# shield.net
KiCad netlist of a schematic drawn in EAGLE
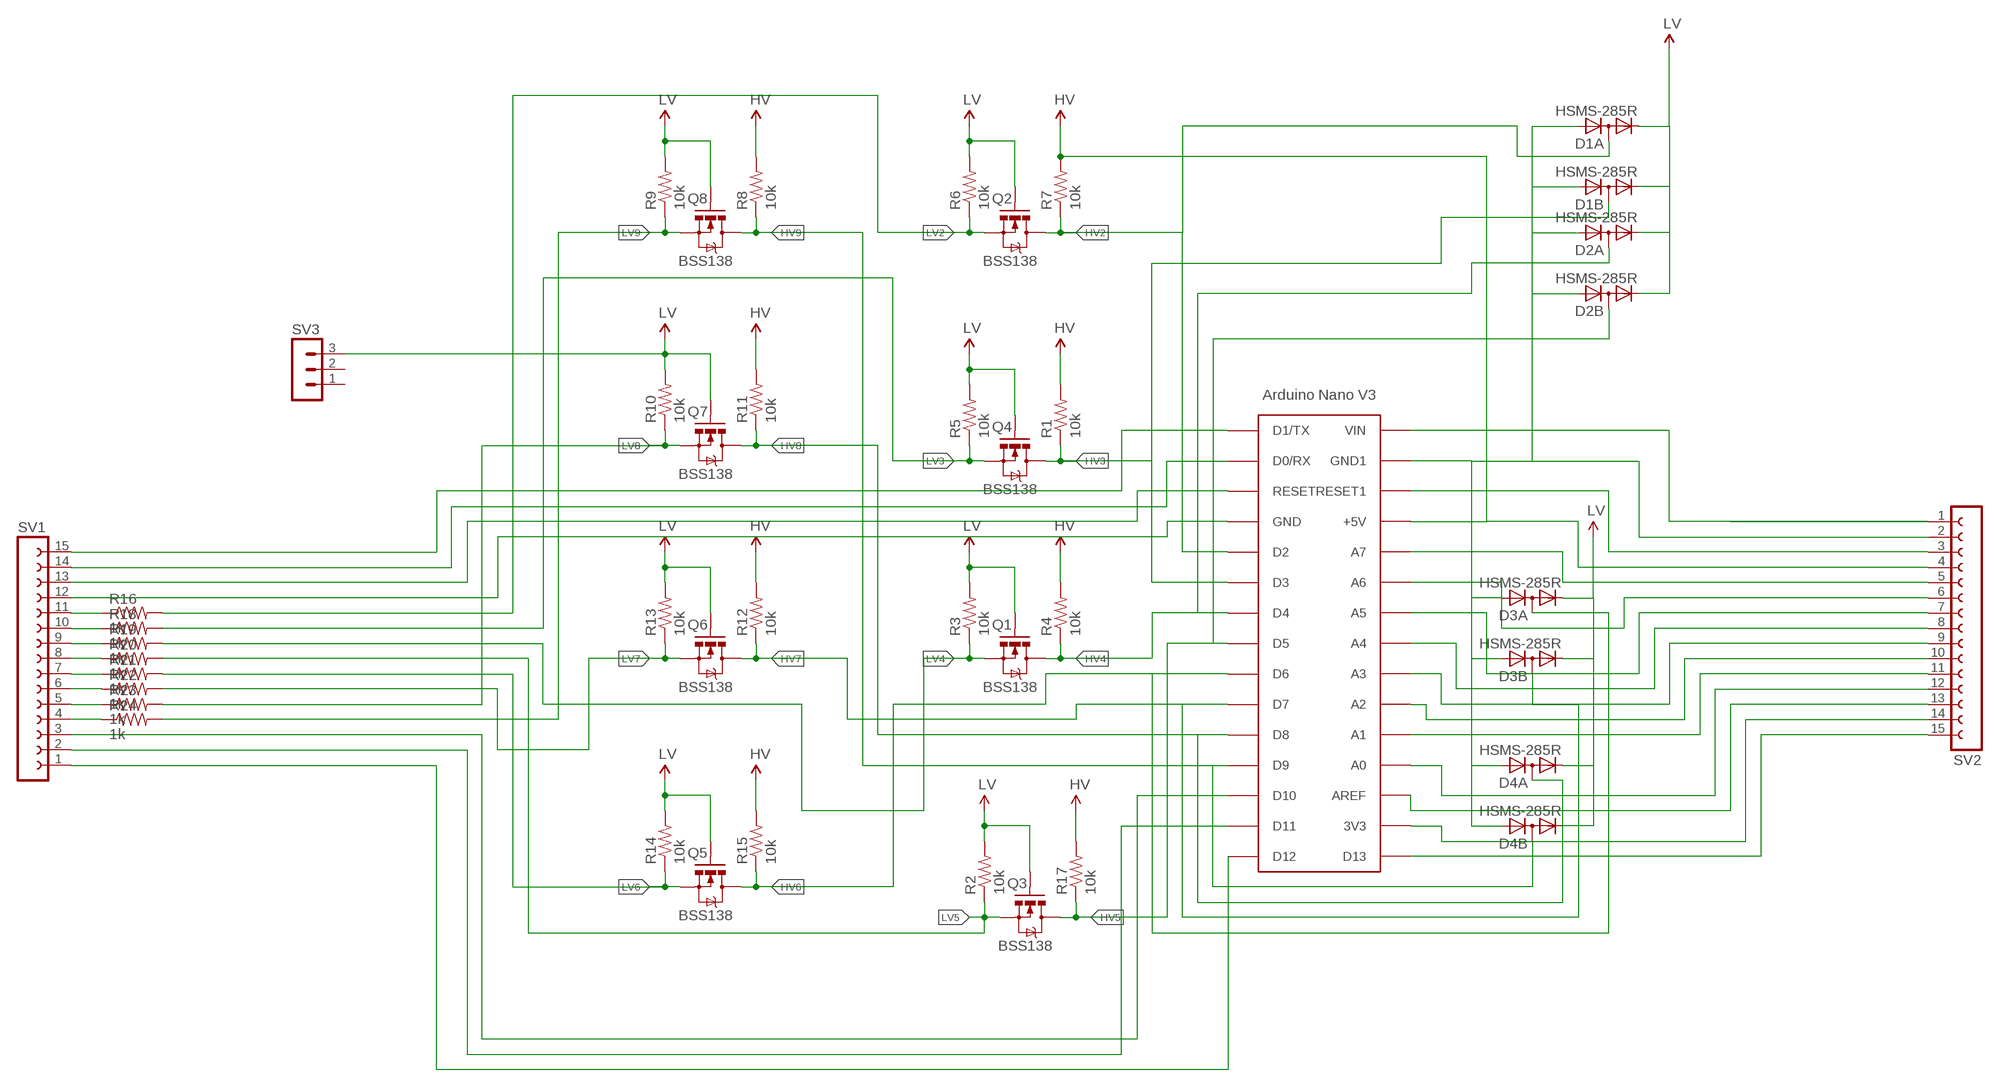
[diagram p0: schematic, sheet 1]

(export (version "E")
  (design (tool "Eeschema 10.0.6"))
  (components
    (comp (ref "D1")
      (value "HSMS-285R")
      (footprint "eagle-import:SOT363")
      (libsource (lib "eagle-import") (part "HSMS-285R"))
    )
    (comp (ref "D2")
      (value "HSMS-285R")
      (footprint "eagle-import:SOT363")
      (libsource (lib "eagle-import") (part "HSMS-285R"))
    )
    (comp (ref "D3")
      (value "HSMS-285R")
      (footprint "eagle-import:SOT363")
      (libsource (lib "eagle-import") (part "HSMS-285R"))
    )
    (comp (ref "D4")
      (value "HSMS-285R")
      (footprint "eagle-import:SOT363")
      (libsource (lib "eagle-import") (part "HSMS-285R"))
    )
    (comp (ref "Q1")
      (value "BSS138")
      (footprint "eagle-import:SOT23-3")
      (libsource (lib "eagle-import") (part "MOSFET-NCHANNELSMD"))
    )
    (comp (ref "Q2")
      (value "BSS138")
      (footprint "eagle-import:SOT23-3")
      (libsource (lib "eagle-import") (part "MOSFET-NCHANNELSMD"))
    )
    (comp (ref "Q3")
      (value "BSS138")
      (footprint "eagle-import:SOT23-3")
      (libsource (lib "eagle-import") (part "MOSFET-NCHANNELSMD"))
    )
    (comp (ref "Q4")
      (value "BSS138")
      (footprint "eagle-import:SOT23-3")
      (libsource (lib "eagle-import") (part "MOSFET-NCHANNELSMD"))
    )
    (comp (ref "Q5")
      (value "BSS138")
      (footprint "eagle-import:SOT23-3")
      (libsource (lib "eagle-import") (part "MOSFET-NCHANNELSMD"))
    )
    (comp (ref "Q6")
      (value "BSS138")
      (footprint "eagle-import:SOT23-3")
      (libsource (lib "eagle-import") (part "MOSFET-NCHANNELSMD"))
    )
    (comp (ref "Q7")
      (value "BSS138")
      (footprint "eagle-import:SOT23-3")
      (libsource (lib "eagle-import") (part "MOSFET-NCHANNELSMD"))
    )
    (comp (ref "Q8")
      (value "BSS138")
      (footprint "eagle-import:SOT23-3")
      (libsource (lib "eagle-import") (part "MOSFET-NCHANNELSMD"))
    )
    (comp (ref "R1")
      (value "10k")
      (footprint "eagle-import:R0402")
      (libsource (lib "eagle-import") (part "R-US_R0402"))
    )
    (comp (ref "R2")
      (value "10k")
      (footprint "eagle-import:R0402")
      (libsource (lib "eagle-import") (part "R-US_R0402"))
    )
    (comp (ref "R3")
      (value "10k")
      (footprint "eagle-import:R0402")
      (libsource (lib "eagle-import") (part "R-US_R0402"))
    )
    (comp (ref "R4")
      (value "10k")
      (footprint "eagle-import:R0402")
      (libsource (lib "eagle-import") (part "R-US_R0402"))
    )
    (comp (ref "R5")
      (value "10k")
      (footprint "eagle-import:R0402")
      (libsource (lib "eagle-import") (part "R-US_R0402"))
    )
    (comp (ref "R6")
      (value "10k")
      (footprint "eagle-import:R0402")
      (libsource (lib "eagle-import") (part "R-US_R0402"))
    )
    (comp (ref "R7")
      (value "10k")
      (footprint "eagle-import:R0402")
      (libsource (lib "eagle-import") (part "R-US_R0402"))
    )
    (comp (ref "R8")
      (value "10k")
      (footprint "eagle-import:R0402")
      (libsource (lib "eagle-import") (part "R-US_R0402"))
    )
    (comp (ref "R9")
      (value "10k")
      (footprint "eagle-import:R0402")
      (libsource (lib "eagle-import") (part "R-US_R0402"))
    )
    (comp (ref "R10")
      (value "10k")
      (footprint "eagle-import:R0402")
      (libsource (lib "eagle-import") (part "R-US_R0402"))
    )
    (comp (ref "R11")
      (value "10k")
      (footprint "eagle-import:R0402")
      (libsource (lib "eagle-import") (part "R-US_R0402"))
    )
    (comp (ref "R12")
      (value "10k")
      (footprint "eagle-import:R0402")
      (libsource (lib "eagle-import") (part "R-US_R0402"))
    )
    (comp (ref "R13")
      (value "10k")
      (footprint "eagle-import:R0402")
      (libsource (lib "eagle-import") (part "R-US_R0402"))
    )
    (comp (ref "R14")
      (value "10k")
      (footprint "eagle-import:R0402")
      (libsource (lib "eagle-import") (part "R-US_R0402"))
    )
    (comp (ref "R15")
      (value "10k")
      (footprint "eagle-import:R0402")
      (libsource (lib "eagle-import") (part "R-US_R0402"))
    )
    (comp (ref "R16")
      (value "1k")
      (footprint "eagle-import:R0402")
      (libsource (lib "eagle-import") (part "R-US_R0402"))
    )
    (comp (ref "R17")
      (value "10k")
      (footprint "eagle-import:R0402")
      (libsource (lib "eagle-import") (part "R-US_R0402"))
    )
    (comp (ref "R18")
      (value "1k")
      (footprint "eagle-import:R0402")
      (libsource (lib "eagle-import") (part "R-US_R0402"))
    )
    (comp (ref "R19")
      (value "1k")
      (footprint "eagle-import:R0402")
      (libsource (lib "eagle-import") (part "R-US_R0402"))
    )
    (comp (ref "R20")
      (value "1k")
      (footprint "eagle-import:R0402")
      (libsource (lib "eagle-import") (part "R-US_R0402"))
    )
    (comp (ref "R21")
      (value "1k")
      (footprint "eagle-import:R0402")
      (libsource (lib "eagle-import") (part "R-US_R0402"))
    )
    (comp (ref "R22")
      (value "1k")
      (footprint "eagle-import:R0402")
      (libsource (lib "eagle-import") (part "R-US_R0402"))
    )
    (comp (ref "R23")
      (value "1k")
      (footprint "eagle-import:R0402")
      (libsource (lib "eagle-import") (part "R-US_R0402"))
    )
    (comp (ref "R24")
      (value "1k")
      (footprint "eagle-import:R0402")
      (libsource (lib "eagle-import") (part "R-US_R0402"))
    )
    (comp (ref "SV1")
      (value "FE15-1")
      (footprint "eagle-import:FE15")
      (libsource (lib "eagle-import") (part "FE15-1"))
    )
    (comp (ref "SV2")
      (value "FE15-1")
      (footprint "eagle-import:FE15")
      (libsource (lib "eagle-import") (part "FE15-1"))
    )
    (comp (ref "SV3")
      (value "MA03-1")
      (footprint "eagle-import:MA03-1")
      (libsource (lib "eagle-import") (part "MA03-1"))
    )
    (comp (ref "U$1")
      (value "ARDUINONANO")
      (footprint "eagle-import:PDIP-32")
      (libsource (lib "eagle-import") (part "ARDUINONANO"))
    )
  )
  (nets
    (net (code "1") (name "HV") (class "Default")
      (node (ref "R1") (pin "2") (pinfunction "2_2") (pintype "passive"))
      (node (ref "R11") (pin "2") (pinfunction "2_2") (pintype "passive"))
      (node (ref "R12") (pin "2") (pinfunction "2_2") (pintype "passive"))
      (node (ref "R15") (pin "2") (pinfunction "2_2") (pintype "passive"))
      (node (ref "R17") (pin "2") (pinfunction "2_2") (pintype "passive"))
      (node (ref "R4") (pin "2") (pinfunction "2_2") (pintype "passive"))
      (node (ref "R7") (pin "2") (pinfunction "2_2") (pintype "passive"))
      (node (ref "R8") (pin "2") (pinfunction "2_2") (pintype "passive"))
      (node (ref "SV2") (pin "4") (pinfunction "4_4") (pintype "passive"))
      (node (ref "U$1") (pin "+5V") (pinfunction "+5V_+5V") (pintype "bidirectional"))
    )
    (net (code "2") (name "HV2") (class "Default")
      (node (ref "D1") (pin "2") (pinfunction "AC_2") (pintype "passive"))
      (node (ref "Q2") (pin "3") (pinfunction "D_3") (pintype "passive"))
      (node (ref "R7") (pin "1") (pinfunction "1_1") (pintype "passive"))
      (node (ref "U$1") (pin "D2") (pinfunction "D2_D2") (pintype "bidirectional"))
    )
    (net (code "3") (name "HV3") (class "Default")
      (node (ref "D1") (pin "5") (pinfunction "AC_5") (pintype "passive"))
      (node (ref "Q4") (pin "3") (pinfunction "D_3") (pintype "passive"))
      (node (ref "R1") (pin "1") (pinfunction "1_1") (pintype "passive"))
      (node (ref "U$1") (pin "D3") (pinfunction "D3_D3") (pintype "bidirectional"))
    )
    (net (code "4") (name "HV4") (class "Default")
      (node (ref "D2") (pin "2") (pinfunction "AC_2") (pintype "passive"))
      (node (ref "Q1") (pin "3") (pinfunction "D_3") (pintype "passive"))
      (node (ref "R4") (pin "1") (pinfunction "1_1") (pintype "passive"))
      (node (ref "U$1") (pin "D4") (pinfunction "D4_D4") (pintype "bidirectional"))
    )
    (net (code "5") (name "HV5") (class "Default")
      (node (ref "D2") (pin "5") (pinfunction "AC_5") (pintype "passive"))
      (node (ref "Q3") (pin "3") (pinfunction "D_3") (pintype "passive"))
      (node (ref "R17") (pin "1") (pinfunction "1_1") (pintype "passive"))
      (node (ref "U$1") (pin "D5") (pinfunction "D5_D5") (pintype "bidirectional"))
    )
    (net (code "6") (name "HV6") (class "Default")
      (node (ref "D3") (pin "2") (pinfunction "AC_2") (pintype "passive"))
      (node (ref "Q5") (pin "3") (pinfunction "D_3") (pintype "passive"))
      (node (ref "R15") (pin "1") (pinfunction "1_1") (pintype "passive"))
      (node (ref "U$1") (pin "D6") (pinfunction "D6_D6") (pintype "bidirectional"))
    )
    (net (code "7") (name "HV7") (class "Default")
      (node (ref "D3") (pin "5") (pinfunction "AC_5") (pintype "passive"))
      (node (ref "Q6") (pin "3") (pinfunction "D_3") (pintype "passive"))
      (node (ref "R12") (pin "1") (pinfunction "1_1") (pintype "passive"))
      (node (ref "U$1") (pin "D7") (pinfunction "D7_D7") (pintype "bidirectional"))
    )
    (net (code "8") (name "HV8") (class "Default")
      (node (ref "D4") (pin "2") (pinfunction "AC_2") (pintype "passive"))
      (node (ref "Q7") (pin "3") (pinfunction "D_3") (pintype "passive"))
      (node (ref "R11") (pin "1") (pinfunction "1_1") (pintype "passive"))
      (node (ref "U$1") (pin "D8") (pinfunction "D8_D8") (pintype "bidirectional"))
    )
    (net (code "9") (name "HV9") (class "Default")
      (node (ref "D4") (pin "5") (pinfunction "AC_5") (pintype "passive"))
      (node (ref "Q8") (pin "3") (pinfunction "D_3") (pintype "passive"))
      (node (ref "R8") (pin "1") (pinfunction "1_1") (pintype "passive"))
      (node (ref "U$1") (pin "D9") (pinfunction "D9_D9") (pintype "bidirectional"))
    )
    (net (code "10") (name "LV") (class "Default")
      (node (ref "D1") (pin "1") (pinfunction "C_1") (pintype "passive"))
      (node (ref "D1") (pin "4") (pinfunction "C_4") (pintype "passive"))
      (node (ref "D2") (pin "1") (pinfunction "C_1") (pintype "passive"))
      (node (ref "D2") (pin "4") (pinfunction "C_4") (pintype "passive"))
      (node (ref "D3") (pin "1") (pinfunction "C_1") (pintype "passive"))
      (node (ref "D3") (pin "4") (pinfunction "C_4") (pintype "passive"))
      (node (ref "D4") (pin "1") (pinfunction "C_1") (pintype "passive"))
      (node (ref "D4") (pin "4") (pinfunction "C_4") (pintype "passive"))
      (node (ref "Q1") (pin "1") (pinfunction "G_1") (pintype "passive"))
      (node (ref "Q2") (pin "1") (pinfunction "G_1") (pintype "passive"))
      (node (ref "Q3") (pin "1") (pinfunction "G_1") (pintype "passive"))
      (node (ref "Q4") (pin "1") (pinfunction "G_1") (pintype "passive"))
      (node (ref "Q5") (pin "1") (pinfunction "G_1") (pintype "passive"))
      (node (ref "Q6") (pin "1") (pinfunction "G_1") (pintype "passive"))
      (node (ref "Q7") (pin "1") (pinfunction "G_1") (pintype "passive"))
      (node (ref "Q8") (pin "1") (pinfunction "G_1") (pintype "passive"))
      (node (ref "R10") (pin "2") (pinfunction "2_2") (pintype "passive"))
      (node (ref "R13") (pin "2") (pinfunction "2_2") (pintype "passive"))
      (node (ref "R14") (pin "2") (pinfunction "2_2") (pintype "passive"))
      (node (ref "R2") (pin "2") (pinfunction "2_2") (pintype "passive"))
      (node (ref "R3") (pin "2") (pinfunction "2_2") (pintype "passive"))
      (node (ref "R5") (pin "2") (pinfunction "2_2") (pintype "passive"))
      (node (ref "R6") (pin "2") (pinfunction "2_2") (pintype "passive"))
      (node (ref "R9") (pin "2") (pinfunction "2_2") (pintype "passive"))
      (node (ref "SV3") (pin "3") (pinfunction "3_3") (pintype "passive"))
    )
    (net (code "11") (name "LV2") (class "Default")
      (node (ref "Q2") (pin "2") (pinfunction "S_2") (pintype "passive"))
      (node (ref "R16") (pin "2") (pinfunction "2_2") (pintype "passive"))
      (node (ref "R6") (pin "1") (pinfunction "1_1") (pintype "passive"))
    )
    (net (code "12") (name "LV3") (class "Default")
      (node (ref "Q4") (pin "2") (pinfunction "S_2") (pintype "passive"))
      (node (ref "R18") (pin "2") (pinfunction "2_2") (pintype "passive"))
      (node (ref "R5") (pin "1") (pinfunction "1_1") (pintype "passive"))
    )
    (net (code "13") (name "LV4") (class "Default")
      (node (ref "Q1") (pin "2") (pinfunction "S_2") (pintype "passive"))
      (node (ref "R19") (pin "2") (pinfunction "2_2") (pintype "passive"))
      (node (ref "R3") (pin "1") (pinfunction "1_1") (pintype "passive"))
    )
    (net (code "14") (name "LV5") (class "Default")
      (node (ref "Q3") (pin "2") (pinfunction "S_2") (pintype "passive"))
      (node (ref "R2") (pin "1") (pinfunction "1_1") (pintype "passive"))
      (node (ref "R20") (pin "2") (pinfunction "2_2") (pintype "passive"))
    )
    (net (code "15") (name "LV6") (class "Default")
      (node (ref "Q5") (pin "2") (pinfunction "S_2") (pintype "passive"))
      (node (ref "R14") (pin "1") (pinfunction "1_1") (pintype "passive"))
      (node (ref "R21") (pin "2") (pinfunction "2_2") (pintype "passive"))
    )
    (net (code "16") (name "LV7") (class "Default")
      (node (ref "Q6") (pin "2") (pinfunction "S_2") (pintype "passive"))
      (node (ref "R13") (pin "1") (pinfunction "1_1") (pintype "passive"))
      (node (ref "R22") (pin "2") (pinfunction "2_2") (pintype "passive"))
    )
    (net (code "17") (name "LV8") (class "Default")
      (node (ref "Q7") (pin "2") (pinfunction "S_2") (pintype "passive"))
      (node (ref "R10") (pin "1") (pinfunction "1_1") (pintype "passive"))
      (node (ref "R23") (pin "2") (pinfunction "2_2") (pintype "passive"))
    )
    (net (code "18") (name "LV9") (class "Default")
      (node (ref "Q8") (pin "2") (pinfunction "S_2") (pintype "passive"))
      (node (ref "R24") (pin "2") (pinfunction "2_2") (pintype "passive"))
      (node (ref "R9") (pin "1") (pinfunction "1_1") (pintype "passive"))
    )
    (net (code "19") (name "Net-(D1A-A)") (class "Default")
      (node (ref "D1") (pin "3") (pinfunction "A_3") (pintype "passive"))
      (node (ref "D1") (pin "6") (pinfunction "A_6") (pintype "passive"))
      (node (ref "D2") (pin "3") (pinfunction "A_3") (pintype "passive"))
      (node (ref "D2") (pin "6") (pinfunction "A_6") (pintype "passive"))
      (node (ref "D3") (pin "3") (pinfunction "A_3") (pintype "passive"))
      (node (ref "D3") (pin "6") (pinfunction "A_6") (pintype "passive"))
      (node (ref "D4") (pin "3") (pinfunction "A_3") (pintype "passive"))
      (node (ref "D4") (pin "6") (pinfunction "A_6") (pintype "passive"))
      (node (ref "SV2") (pin "2") (pinfunction "2_2") (pintype "passive"))
      (node (ref "U$1") (pin "GND1") (pinfunction "GND1_GND1") (pintype "bidirectional"))
    )
    (net (code "20") (name "Net-(R16-Pad1)") (class "Default")
      (node (ref "R16") (pin "1") (pinfunction "1_1") (pintype "passive"))
      (node (ref "SV1") (pin "11") (pinfunction "11_11") (pintype "passive"))
    )
    (net (code "21") (name "Net-(R18-Pad1)") (class "Default")
      (node (ref "R18") (pin "1") (pinfunction "1_1") (pintype "passive"))
      (node (ref "SV1") (pin "10") (pinfunction "10_10") (pintype "passive"))
    )
    (net (code "22") (name "Net-(R19-Pad1)") (class "Default")
      (node (ref "R19") (pin "1") (pinfunction "1_1") (pintype "passive"))
      (node (ref "SV1") (pin "9") (pinfunction "9_9") (pintype "passive"))
    )
    (net (code "23") (name "Net-(R20-Pad1)") (class "Default")
      (node (ref "R20") (pin "1") (pinfunction "1_1") (pintype "passive"))
      (node (ref "SV1") (pin "8") (pinfunction "8_8") (pintype "passive"))
    )
    (net (code "24") (name "Net-(R21-Pad1)") (class "Default")
      (node (ref "R21") (pin "1") (pinfunction "1_1") (pintype "passive"))
      (node (ref "SV1") (pin "7") (pinfunction "7_7") (pintype "passive"))
    )
    (net (code "25") (name "Net-(R22-Pad1)") (class "Default")
      (node (ref "R22") (pin "1") (pinfunction "1_1") (pintype "passive"))
      (node (ref "SV1") (pin "6") (pinfunction "6_6") (pintype "passive"))
    )
    (net (code "26") (name "Net-(R23-Pad1)") (class "Default")
      (node (ref "R23") (pin "1") (pinfunction "1_1") (pintype "passive"))
      (node (ref "SV1") (pin "5") (pinfunction "5_5") (pintype "passive"))
    )
    (net (code "27") (name "Net-(R24-Pad1)") (class "Default")
      (node (ref "R24") (pin "1") (pinfunction "1_1") (pintype "passive"))
      (node (ref "SV1") (pin "4") (pinfunction "4_4") (pintype "passive"))
    )
    (net (code "28") (name "Net-(SV1-Pad1)") (class "Default")
      (node (ref "SV1") (pin "1") (pinfunction "1_1") (pintype "passive"))
      (node (ref "U$1") (pin "D12") (pinfunction "D12_D12") (pintype "bidirectional"))
    )
    (net (code "29") (name "Net-(SV1-Pad2)") (class "Default")
      (node (ref "SV1") (pin "2") (pinfunction "2_2") (pintype "passive"))
      (node (ref "U$1") (pin "D11") (pinfunction "D11_D11") (pintype "bidirectional"))
    )
    (net (code "30") (name "Net-(SV1-Pad3)") (class "Default")
      (node (ref "SV1") (pin "3") (pinfunction "3_3") (pintype "passive"))
      (node (ref "U$1") (pin "D10") (pinfunction "D10_D10") (pintype "bidirectional"))
    )
    (net (code "31") (name "Net-(SV1-Pad12)") (class "Default")
      (node (ref "SV1") (pin "12") (pinfunction "12_12") (pintype "passive"))
      (node (ref "U$1") (pin "GND") (pinfunction "GND_GND") (pintype "bidirectional"))
    )
    (net (code "32") (name "Net-(SV1-Pad13)") (class "Default")
      (node (ref "SV1") (pin "13") (pinfunction "13_13") (pintype "passive"))
      (node (ref "U$1") (pin "RESET") (pinfunction "RESET_RESET") (pintype "bidirectional"))
    )
    (net (code "33") (name "Net-(SV1-Pad14)") (class "Default")
      (node (ref "SV1") (pin "14") (pinfunction "14_14") (pintype "passive"))
      (node (ref "U$1") (pin "D0/RX") (pinfunction "D0/RX_D0/RX") (pintype "bidirectional"))
    )
    (net (code "34") (name "Net-(SV1-Pad15)") (class "Default")
      (node (ref "SV1") (pin "15") (pinfunction "15_15") (pintype "passive"))
      (node (ref "U$1") (pin "D1/TX") (pinfunction "D1/TX_D1/TX") (pintype "bidirectional"))
    )
    (net (code "35") (name "Net-(SV2-Pad1)") (class "Default")
      (node (ref "SV2") (pin "1") (pinfunction "1_1") (pintype "passive"))
      (node (ref "U$1") (pin "VIN") (pinfunction "VIN_VIN") (pintype "bidirectional"))
    )
    (net (code "36") (name "Net-(SV2-Pad3)") (class "Default")
      (node (ref "SV2") (pin "3") (pinfunction "3_3") (pintype "passive"))
      (node (ref "U$1") (pin "RESET1") (pinfunction "RESET1_RESET1") (pintype "bidirectional"))
    )
    (net (code "37") (name "Net-(SV2-Pad13)") (class "Default")
      (node (ref "SV2") (pin "13") (pinfunction "13_13") (pintype "passive"))
      (node (ref "U$1") (pin "AREF") (pinfunction "AREF_AREF") (pintype "bidirectional"))
    )
    (net (code "38") (name "Net-(SV2-Pad14)") (class "Default")
      (node (ref "SV2") (pin "14") (pinfunction "14_14") (pintype "passive"))
      (node (ref "U$1") (pin "3V3") (pinfunction "3V3_3V3") (pintype "bidirectional"))
    )
    (net (code "39") (name "Net-(SV2-Pad15)") (class "Default")
      (node (ref "SV2") (pin "15") (pinfunction "15_15") (pintype "passive"))
      (node (ref "U$1") (pin "D13") (pinfunction "D13_D13") (pintype "bidirectional"))
    )
    (net (code "40") (name "Net-(U$1-A0)") (class "Default")
      (node (ref "SV2") (pin "12") (pinfunction "12_12") (pintype "passive"))
      (node (ref "U$1") (pin "A7") (pinfunction "A0_A7") (pintype "bidirectional"))
    )
    (net (code "41") (name "Net-(U$1-A1)") (class "Default")
      (node (ref "SV2") (pin "11") (pinfunction "11_11") (pintype "passive"))
      (node (ref "U$1") (pin "A6") (pinfunction "A1_A6") (pintype "bidirectional"))
    )
    (net (code "42") (name "Net-(U$1-A2)") (class "Default")
      (node (ref "SV2") (pin "10") (pinfunction "10_10") (pintype "passive"))
      (node (ref "U$1") (pin "A5") (pinfunction "A2_A5") (pintype "bidirectional"))
    )
    (net (code "43") (name "Net-(U$1-A3)") (class "Default")
      (node (ref "SV2") (pin "9") (pinfunction "9_9") (pintype "passive"))
      (node (ref "U$1") (pin "A4") (pinfunction "A3_A4") (pintype "bidirectional"))
    )
    (net (code "44") (name "Net-(U$1-A4)") (class "Default")
      (node (ref "SV2") (pin "8") (pinfunction "8_8") (pintype "passive"))
      (node (ref "U$1") (pin "A3") (pinfunction "A4_A3") (pintype "bidirectional"))
    )
    (net (code "45") (name "Net-(U$1-A5)") (class "Default")
      (node (ref "SV2") (pin "7") (pinfunction "7_7") (pintype "passive"))
      (node (ref "U$1") (pin "A2") (pinfunction "A5_A2") (pintype "bidirectional"))
    )
    (net (code "46") (name "Net-(U$1-A6)") (class "Default")
      (node (ref "SV2") (pin "6") (pinfunction "6_6") (pintype "passive"))
      (node (ref "U$1") (pin "A1") (pinfunction "A6_A1") (pintype "bidirectional"))
    )
    (net (code "47") (name "Net-(U$1-A7)") (class "Default")
      (node (ref "SV2") (pin "5") (pinfunction "5_5") (pintype "passive"))
      (node (ref "U$1") (pin "A0") (pinfunction "A7_A0") (pintype "bidirectional"))
    )
    (net (code "48") (name "unconnected-(SV3-Pad1)") (class "Default")
      (node (ref "SV3") (pin "1") (pinfunction "1_1") (pintype "passive"))
    )
    (net (code "49") (name "unconnected-(SV3-Pad2)") (class "Default")
      (node (ref "SV3") (pin "2") (pinfunction "2_2") (pintype "passive"))
    )
  )
)
